# Lab_1.net
KiCad netlist of a schematic drawn in EAGLE
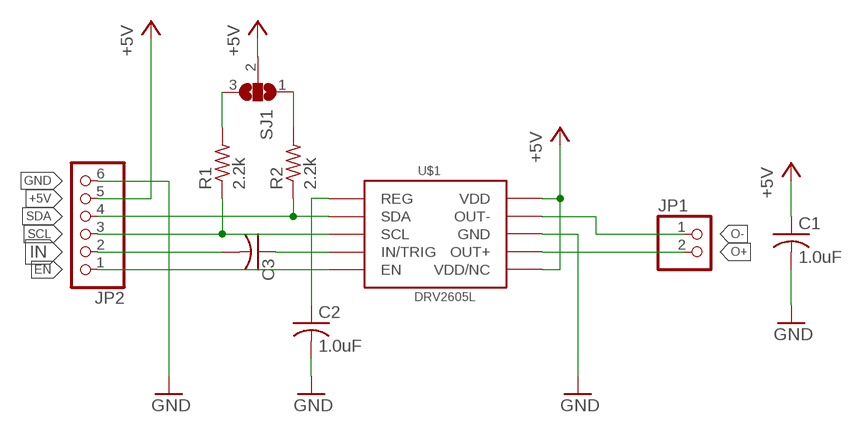
[diagram p0: schematic, sheet 1]

(export (version "E")
  (design (tool "Eeschema 10.0.6"))
  (components
    (comp (ref "C1")
      (value "1.0uF")
      (footprint "eagle-import:C0805")
      (libsource (lib "eagle-import") (part "C-USC0805"))
    )
    (comp (ref "C2")
      (value "1.0uF")
      (footprint "eagle-import:C0805")
      (libsource (lib "eagle-import") (part "C-USC0805"))
    )
    (comp (ref "C3")
      (value "C-USC0805")
      (footprint "eagle-import:C0805")
      (libsource (lib "eagle-import") (part "C-USC0805"))
    )
    (comp (ref "JP1")
      (value "PINHD-1X2")
      (footprint "eagle-import:1X02")
      (libsource (lib "eagle-import") (part "PINHD-1X2"))
    )
    (comp (ref "JP2")
      (value "PINHD-1X6")
      (footprint "eagle-import:1X06")
      (libsource (lib "eagle-import") (part "PINHD-1X6"))
    )
    (comp (ref "R1")
      (value "2.2k")
      (footprint "eagle-import:R0805")
      (libsource (lib "eagle-import") (part "R-US_R0805"))
    )
    (comp (ref "R2")
      (value "2.2k")
      (footprint "eagle-import:R0805")
      (libsource (lib "eagle-import") (part "R-US_R0805"))
    )
    (comp (ref "SJ1")
      (value "SJ2W")
      (footprint "eagle-import:SJ_2")
      (libsource (lib "eagle-import") (part "SJ2W"))
    )
    (comp (ref "U$1")
      (value "DRV2605L")
      (footprint "eagle-import:VSSOP-10")
      (libsource (lib "eagle-import") (part "DRV2605L"))
    )
  )
  (nets
    (net (code "1") (name "+5V") (class "Default")
      (node (ref "C1") (pin "1") (pinfunction "1_1") (pintype "passive"))
      (node (ref "JP2") (pin "5") (pinfunction "5_5") (pintype "passive"))
      (node (ref "SJ1") (pin "2") (pinfunction "2_2") (pintype "passive"))
      (node (ref "U$1") (pin "P$10") (pinfunction "VDD_P$10") (pintype "bidirectional"))
      (node (ref "U$1") (pin "P$6") (pinfunction "VDD/NC_P$6") (pintype "bidirectional"))
    )
    (net (code "2") (name "EN") (class "Default")
      (node (ref "JP2") (pin "1") (pinfunction "1_1") (pintype "passive"))
      (node (ref "U$1") (pin "P$5") (pinfunction "EN_P$5") (pintype "bidirectional"))
    )
    (net (code "3") (name "GND") (class "Default")
      (node (ref "C1") (pin "2") (pinfunction "2_2") (pintype "passive"))
      (node (ref "C2") (pin "2") (pinfunction "2_2") (pintype "passive"))
      (node (ref "JP2") (pin "6") (pinfunction "6_6") (pintype "passive"))
      (node (ref "U$1") (pin "P$8") (pinfunction "GND_P$8") (pintype "bidirectional"))
    )
    (net (code "4") (name "IN") (class "Default")
      (node (ref "C3") (pin "2") (pinfunction "2_2") (pintype "passive"))
      (node (ref "JP2") (pin "2") (pinfunction "2_2") (pintype "passive"))
    )
    (net (code "5") (name "Net-(R1-Pad2)") (class "Default")
      (node (ref "R1") (pin "2") (pinfunction "2_2") (pintype "passive"))
      (node (ref "SJ1") (pin "3") (pinfunction "3_3") (pintype "passive"))
    )
    (net (code "6") (name "Net-(R2-Pad2)") (class "Default")
      (node (ref "R2") (pin "2") (pinfunction "2_2") (pintype "passive"))
      (node (ref "SJ1") (pin "1") (pinfunction "1_1") (pintype "passive"))
    )
    (net (code "7") (name "Net-(U$1-IN{slash}TRIG)") (class "Default")
      (node (ref "C3") (pin "1") (pinfunction "1_1") (pintype "passive"))
      (node (ref "U$1") (pin "P$4") (pinfunction "IN/TRIG_P$4") (pintype "bidirectional"))
    )
    (net (code "8") (name "Net-(U$1-REG)") (class "Default")
      (node (ref "C2") (pin "1") (pinfunction "1_1") (pintype "passive"))
      (node (ref "U$1") (pin "P$1") (pinfunction "REG_P$1") (pintype "bidirectional"))
    )
    (net (code "9") (name "O+") (class "Default")
      (node (ref "JP1") (pin "2") (pinfunction "2_2") (pintype "passive"))
      (node (ref "U$1") (pin "P$7") (pinfunction "OUT+_P$7") (pintype "bidirectional"))
    )
    (net (code "10") (name "O-") (class "Default")
      (node (ref "JP1") (pin "1") (pinfunction "1_1") (pintype "passive"))
      (node (ref "U$1") (pin "P$9") (pinfunction "OUT-_P$9") (pintype "bidirectional"))
    )
    (net (code "11") (name "SCL") (class "Default")
      (node (ref "JP2") (pin "3") (pinfunction "3_3") (pintype "passive"))
      (node (ref "R1") (pin "1") (pinfunction "1_1") (pintype "passive"))
      (node (ref "U$1") (pin "P$2") (pinfunction "SCL_P$2") (pintype "bidirectional"))
    )
    (net (code "12") (name "SDA") (class "Default")
      (node (ref "JP2") (pin "4") (pinfunction "4_4") (pintype "passive"))
      (node (ref "R2") (pin "1") (pinfunction "1_1") (pintype "passive"))
      (node (ref "U$1") (pin "P$3") (pinfunction "SDA_P$3") (pintype "bidirectional"))
    )
  )
)
